# DAC.net
KiCad netlist of a schematic drawn in Altium Designer
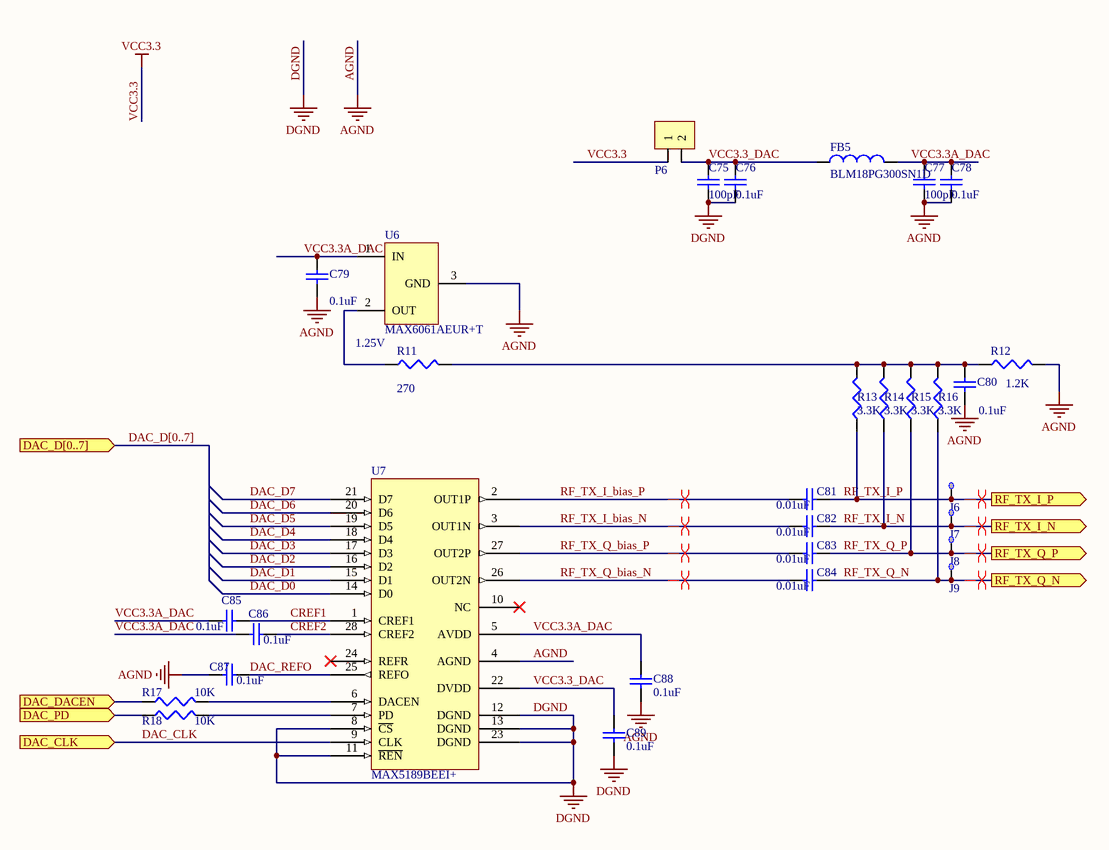
[diagram p0: DAC.SchDoc]

(export (version "E")
  (design (tool "Eeschema 10.0.6"))
  (components
    (comp (ref "C75")
      (value "100pF")
      (footprint "0402")
      (description "Capacitor (Semiconductor SIM Model)")
      (fields (field (name "PUBLISHER") "Altium Limited"))
      (libsource (lib "Miscellaneous Devices") (part "Cap Semi"))
    )
    (comp (ref "C76")
      (value "0.1uF")
      (footprint "0402")
      (description "Capacitor (Semiconductor SIM Model)")
      (fields (field (name "PUBLISHER") "Altium Limited"))
      (libsource (lib "Miscellaneous Devices") (part "Cap Semi"))
    )
    (comp (ref "C77")
      (value "100pF")
      (footprint "0402")
      (description "Capacitor (Semiconductor SIM Model)")
      (fields (field (name "PUBLISHER") "Altium Limited"))
      (libsource (lib "Miscellaneous Devices") (part "Cap Semi"))
    )
    (comp (ref "C78")
      (value "0.1uF")
      (footprint "0402")
      (description "Capacitor (Semiconductor SIM Model)")
      (fields (field (name "PUBLISHER") "Altium Limited"))
      (libsource (lib "Miscellaneous Devices") (part "Cap Semi"))
    )
    (comp (ref "C79")
      (value "0.1uF")
      (footprint "0402")
      (description "Capacitor (Semiconductor SIM Model)")
      (fields (field (name "PUBLISHER") "Altium Limited"))
      (libsource (lib "Miscellaneous Devices") (part "Cap Semi"))
    )
    (comp (ref "C80")
      (value "0.1uF")
      (footprint "0402")
      (description "Capacitor (Semiconductor SIM Model)")
      (fields (field (name "PUBLISHER") "Altium Limited"))
      (libsource (lib "Miscellaneous Devices") (part "Cap Semi"))
    )
    (comp (ref "C81")
      (value "0.01uF")
      (footprint "0402")
      (description "Capacitor (Semiconductor SIM Model)")
      (fields (field (name "PUBLISHER") "Altium Limited"))
      (libsource (lib "Miscellaneous Devices") (part "Cap Semi"))
    )
    (comp (ref "C82")
      (value "0.01uF")
      (footprint "0402")
      (description "Capacitor (Semiconductor SIM Model)")
      (fields (field (name "PUBLISHER") "Altium Limited"))
      (libsource (lib "Miscellaneous Devices") (part "Cap Semi"))
    )
    (comp (ref "C83")
      (value "0.01uF")
      (footprint "0402")
      (description "Capacitor (Semiconductor SIM Model)")
      (fields (field (name "PUBLISHER") "Altium Limited"))
      (libsource (lib "Miscellaneous Devices") (part "Cap Semi"))
    )
    (comp (ref "C84")
      (value "0.01uF")
      (footprint "0402")
      (description "Capacitor (Semiconductor SIM Model)")
      (fields (field (name "PUBLISHER") "Altium Limited"))
      (libsource (lib "Miscellaneous Devices") (part "Cap Semi"))
    )
    (comp (ref "C85")
      (value "0.1uF")
      (footprint "0402")
      (description "Capacitor (Semiconductor SIM Model)")
      (fields (field (name "PUBLISHER") "Altium Limited"))
      (libsource (lib "Miscellaneous Devices") (part "Cap Semi"))
    )
    (comp (ref "C86")
      (value "0.1uF")
      (footprint "0402")
      (description "Capacitor (Semiconductor SIM Model)")
      (fields (field (name "PUBLISHER") "Altium Limited"))
      (libsource (lib "Miscellaneous Devices") (part "Cap Semi"))
    )
    (comp (ref "C87")
      (value "0.1uF")
      (footprint "0402")
      (description "Capacitor (Semiconductor SIM Model)")
      (fields (field (name "PUBLISHER") "Altium Limited"))
      (libsource (lib "Miscellaneous Devices") (part "Cap Semi"))
    )
    (comp (ref "C88")
      (value "0.1uF")
      (footprint "0402")
      (description "Capacitor (Semiconductor SIM Model)")
      (fields (field (name "PUBLISHER") "Altium Limited"))
      (libsource (lib "Miscellaneous Devices") (part "Cap Semi"))
    )
    (comp (ref "C89")
      (value "0.1uF")
      (footprint "0402")
      (description "Capacitor (Semiconductor SIM Model)")
      (fields (field (name "PUBLISHER") "Altium Limited"))
      (libsource (lib "Miscellaneous Devices") (part "Cap Semi"))
    )
    (comp (ref "FB5")
      (value "BLM18PG300SN1D")
      (footprint "1608[0603]")
      (description "FERRITE CHIP 30 OHM 1000MA 0603")
      (libsource (lib "SDR") (part "Ferrite Bead"))
    )
    (comp (ref "J6")
      (value "5004")
      (footprint "TestPoint")
      (description "TEST POINT PC MINI .040\"D YELLOW")
      (libsource (lib "SDR") (part "TestPoint"))
    )
    (comp (ref "J7")
      (value "5004")
      (footprint "TestPoint")
      (description "TEST POINT PC MINI .040\"D YELLOW")
      (libsource (lib "SDR") (part "TestPoint"))
    )
    (comp (ref "J8")
      (value "5004")
      (footprint "TestPoint")
      (description "TEST POINT PC MINI .040\"D YELLOW")
      (libsource (lib "SDR") (part "TestPoint"))
    )
    (comp (ref "J9")
      (value "5004")
      (footprint "TestPoint")
      (description "TEST POINT PC MINI .040\"D YELLOW")
      (libsource (lib "SDR") (part "TestPoint"))
    )
    (comp (ref "P6")
      (value "1 x 2 header")
      (footprint "1x2 header")
      (description "100 mils standard header")
      (libsource (lib "SDR") (part "1 x 2 header"))
    )
    (comp (ref "R11")
      (value "270")
      (footprint "0402")
      (description "Resistor")
      (fields (field (name "PUBLISHER") "Altium Limited"))
      (libsource (lib "Miscellaneous Devices") (part "Res3"))
    )
    (comp (ref "R12")
      (value "1.2K")
      (footprint "0402")
      (description "Resistor")
      (fields (field (name "PUBLISHER") "Altium Limited"))
      (libsource (lib "Miscellaneous Devices") (part "Res3"))
    )
    (comp (ref "R13")
      (value "3.3K")
      (footprint "0402")
      (description "Resistor")
      (fields (field (name "PUBLISHER") "Altium Limited"))
      (libsource (lib "Miscellaneous Devices") (part "Res3"))
    )
    (comp (ref "R14")
      (value "3.3K")
      (footprint "0402")
      (description "Resistor")
      (fields (field (name "PUBLISHER") "Altium Limited"))
      (libsource (lib "Miscellaneous Devices") (part "Res3"))
    )
    (comp (ref "R15")
      (value "3.3K")
      (footprint "0402")
      (description "Resistor")
      (fields (field (name "PUBLISHER") "Altium Limited"))
      (libsource (lib "Miscellaneous Devices") (part "Res3"))
    )
    (comp (ref "R16")
      (value "3.3K")
      (footprint "0402")
      (description "Resistor")
      (fields (field (name "PUBLISHER") "Altium Limited"))
      (libsource (lib "Miscellaneous Devices") (part "Res3"))
    )
    (comp (ref "R17")
      (value "10K")
      (footprint "0402")
      (description "Resistor")
      (fields (field (name "PUBLISHER") "Altium Limited"))
      (libsource (lib "Miscellaneous Devices") (part "Res3"))
    )
    (comp (ref "R18")
      (value "10K")
      (footprint "0402")
      (description "Resistor")
      (fields (field (name "PUBLISHER") "Altium Limited"))
      (libsource (lib "Miscellaneous Devices") (part "Res3"))
    )
    (comp (ref "U6")
      (value "MAX6061AEUR+T")
      (footprint "SOT23-3N")
      (description "IC REF VOLT LDO SOT23-3")
      (fields (field (name "ALTIUM_VALUE") "1.25V"))
      (libsource (lib "SDR") (part "MAX6061"))
    )
    (comp (ref "U7")
      (value "MAX5189BEEI+")
      (footprint "SOP63P600X173-28N")
      (description "IC DAC 8BIT DUAL 40MHZ 28-QSOP")
      (libsource (lib "SDR") (part "MAX5189"))
    )
  )
  (nets
    (net (code "1") (name "/CREF1") (class "Default")
      (node (ref "C85") (pin "2") (pinfunction "2_2") (pintype "passive"))
      (node (ref "U7") (pin "1") (pinfunction "CREF1_1") (pintype "input"))
    )
    (net (code "2") (name "/CREF2") (class "Default")
      (node (ref "C86") (pin "2") (pinfunction "2_2") (pintype "passive"))
      (node (ref "U7") (pin "28") (pinfunction "CREF2_28") (pintype "input"))
    )
    (net (code "3") (name "/DAC_CLK") (class "Default")
      (node (ref "U7") (pin "9") (pinfunction "CLK_9") (pintype "input"))
    )
    (net (code "4") (name "/DAC_D0") (class "Default")
      (node (ref "U7") (pin "14") (pinfunction "D0_14") (pintype "input"))
    )
    (net (code "5") (name "/DAC_D1") (class "Default")
      (node (ref "U7") (pin "15") (pinfunction "D1_15") (pintype "input"))
    )
    (net (code "6") (name "/DAC_D2") (class "Default")
      (node (ref "U7") (pin "16") (pinfunction "D2_16") (pintype "input"))
    )
    (net (code "7") (name "/DAC_D3") (class "Default")
      (node (ref "U7") (pin "17") (pinfunction "D3_17") (pintype "input"))
    )
    (net (code "8") (name "/DAC_D4") (class "Default")
      (node (ref "U7") (pin "18") (pinfunction "D4_18") (pintype "input"))
    )
    (net (code "9") (name "/DAC_D5") (class "Default")
      (node (ref "U7") (pin "19") (pinfunction "D5_19") (pintype "input"))
    )
    (net (code "10") (name "/DAC_D6") (class "Default")
      (node (ref "U7") (pin "20") (pinfunction "D6_20") (pintype "input"))
    )
    (net (code "11") (name "/DAC_D7") (class "Default")
      (node (ref "U7") (pin "21") (pinfunction "D7_21") (pintype "input"))
    )
    (net (code "12") (name "/DAC_DACEN") (class "Default")
      (node (ref "R17") (pin "1") (pinfunction "1_1") (pintype "passive"))
    )
    (net (code "14") (name "/DAC_PD") (class "Default")
      (node (ref "R18") (pin "1") (pinfunction "1_1") (pintype "passive"))
    )
    (net (code "15") (name "/DAC_REFO") (class "Default")
      (node (ref "C87") (pin "2") (pinfunction "2_2") (pintype "passive"))
      (node (ref "U7") (pin "25") (pinfunction "REFO_25") (pintype "output"))
    )
    (net (code "16") (name "/RF_TX_I_N") (class "Default")
      (node (ref "C82") (pin "2") (pinfunction "2_2") (pintype "passive"))
      (node (ref "J7") (pin "1") (pinfunction "TB_1") (pintype "passive"))
      (node (ref "R14") (pin "1") (pinfunction "1_1") (pintype "passive"))
    )
    (net (code "17") (name "/RF_TX_I_P") (class "Default")
      (node (ref "C81") (pin "2") (pinfunction "2_2") (pintype "passive"))
      (node (ref "J6") (pin "1") (pinfunction "TB_1") (pintype "passive"))
      (node (ref "R13") (pin "1") (pinfunction "1_1") (pintype "passive"))
    )
    (net (code "18") (name "/RF_TX_I_bias_N") (class "Default")
      (node (ref "C82") (pin "1") (pinfunction "1_1") (pintype "passive"))
      (node (ref "U7") (pin "3") (pinfunction "OUT1N_3") (pintype "output"))
    )
    (net (code "19") (name "/RF_TX_I_bias_P") (class "Default")
      (node (ref "C81") (pin "1") (pinfunction "1_1") (pintype "passive"))
      (node (ref "U7") (pin "2") (pinfunction "OUT1P_2") (pintype "output"))
    )
    (net (code "20") (name "/RF_TX_Q_N") (class "Default")
      (node (ref "C84") (pin "2") (pinfunction "2_2") (pintype "passive"))
      (node (ref "J9") (pin "1") (pinfunction "TB_1") (pintype "passive"))
      (node (ref "R16") (pin "1") (pinfunction "1_1") (pintype "passive"))
    )
    (net (code "21") (name "/RF_TX_Q_P") (class "Default")
      (node (ref "C83") (pin "2") (pinfunction "2_2") (pintype "passive"))
      (node (ref "J8") (pin "1") (pinfunction "TB_1") (pintype "passive"))
      (node (ref "R15") (pin "1") (pinfunction "1_1") (pintype "passive"))
    )
    (net (code "22") (name "/RF_TX_Q_bias_N") (class "Default")
      (node (ref "C84") (pin "1") (pinfunction "1_1") (pintype "passive"))
      (node (ref "U7") (pin "26") (pinfunction "OUT2N_26") (pintype "output"))
    )
    (net (code "23") (name "/RF_TX_Q_bias_P") (class "Default")
      (node (ref "C83") (pin "1") (pinfunction "1_1") (pintype "passive"))
      (node (ref "U7") (pin "27") (pinfunction "OUT2P_27") (pintype "output"))
    )
    (net (code "24") (name "/VCC3.3A_DAC") (class "Default")
      (node (ref "C77") (pin "2") (pinfunction "2_2") (pintype "passive"))
      (node (ref "C78") (pin "2") (pinfunction "2_2") (pintype "passive"))
      (node (ref "C79") (pin "2") (pinfunction "2_2") (pintype "passive"))
      (node (ref "C85") (pin "1") (pinfunction "1_1") (pintype "passive"))
      (node (ref "C86") (pin "1") (pinfunction "1_1") (pintype "passive"))
      (node (ref "C88") (pin "1") (pinfunction "1_1") (pintype "passive"))
      (node (ref "FB5") (pin "2") (pinfunction "2_2") (pintype "passive"))
      (node (ref "U6") (pin "1") (pinfunction "IN_1") (pintype "passive"))
      (node (ref "U7") (pin "5") (pinfunction "AVDD_5") (pintype "power_in"))
    )
    (net (code "25") (name "/VCC3.3_DAC") (class "Default")
      (node (ref "C75") (pin "2") (pinfunction "2_2") (pintype "passive"))
      (node (ref "C76") (pin "2") (pinfunction "2_2") (pintype "passive"))
      (node (ref "C89") (pin "1") (pinfunction "1_1") (pintype "passive"))
      (node (ref "FB5") (pin "1") (pinfunction "1_1") (pintype "passive"))
      (node (ref "P6") (pin "2") (pinfunction "2_2") (pintype "passive"))
      (node (ref "U7") (pin "22") (pinfunction "DVDD_22") (pintype "power_in"))
    )
    (net (code "26") (name "AGND") (class "Default")
      (node (ref "C77") (pin "1") (pinfunction "1_1") (pintype "passive"))
      (node (ref "C78") (pin "1") (pinfunction "1_1") (pintype "passive"))
      (node (ref "C79") (pin "1") (pinfunction "1_1") (pintype "passive"))
      (node (ref "C80") (pin "1") (pinfunction "1_1") (pintype "passive"))
      (node (ref "C87") (pin "1") (pinfunction "1_1") (pintype "passive"))
      (node (ref "C88") (pin "2") (pinfunction "2_2") (pintype "passive"))
      (node (ref "R12") (pin "2") (pinfunction "2_2") (pintype "passive"))
      (node (ref "U6") (pin "3") (pinfunction "GND_3") (pintype "power_in"))
      (node (ref "U7") (pin "4") (pinfunction "AGND_4") (pintype "power_in"))
    )
    (net (code "27") (name "DGND") (class "Default")
      (node (ref "C75") (pin "1") (pinfunction "1_1") (pintype "passive"))
      (node (ref "C76") (pin "1") (pinfunction "1_1") (pintype "passive"))
      (node (ref "C89") (pin "2") (pinfunction "2_2") (pintype "passive"))
      (node (ref "U7") (pin "11") (pinfunction "~{REN}_11") (pintype "input"))
      (node (ref "U7") (pin "12") (pinfunction "DGND_12") (pintype "power_in"))
      (node (ref "U7") (pin "13") (pinfunction "DGND_13") (pintype "power_in"))
      (node (ref "U7") (pin "23") (pinfunction "DGND_23") (pintype "power_in"))
      (node (ref "U7") (pin "8") (pinfunction "~{CS}_8") (pintype "input"))
    )
    (net (code "28") (name "Net-(C80-Pad2)") (class "Default")
      (node (ref "C80") (pin "2") (pinfunction "2_2") (pintype "passive"))
      (node (ref "R11") (pin "2") (pinfunction "2_2") (pintype "passive"))
      (node (ref "R12") (pin "1") (pinfunction "1_1") (pintype "passive"))
      (node (ref "R13") (pin "2") (pinfunction "2_2") (pintype "passive"))
      (node (ref "R14") (pin "2") (pinfunction "2_2") (pintype "passive"))
      (node (ref "R15") (pin "2") (pinfunction "2_2") (pintype "passive"))
      (node (ref "R16") (pin "2") (pinfunction "2_2") (pintype "passive"))
    )
    (net (code "29") (name "Net-(U6-OUT)") (class "Default")
      (node (ref "R11") (pin "1") (pinfunction "1_1") (pintype "passive"))
      (node (ref "U6") (pin "2") (pinfunction "OUT_2") (pintype "passive"))
    )
    (net (code "30") (name "Net-(U7-DACEN)") (class "Default")
      (node (ref "R17") (pin "2") (pinfunction "2_2") (pintype "passive"))
      (node (ref "U7") (pin "6") (pinfunction "DACEN_6") (pintype "input"))
    )
    (net (code "31") (name "Net-(U7-PD)") (class "Default")
      (node (ref "R18") (pin "2") (pinfunction "2_2") (pintype "passive"))
      (node (ref "U7") (pin "7") (pinfunction "PD_7") (pintype "input"))
    )
    (net (code "32") (name "VCC3.3") (class "Default")
      (node (ref "P6") (pin "1") (pinfunction "1_1") (pintype "passive"))
    )
    (net (code "33") (name "unconnected-(U7-NC-Pad10)") (class "Default")
      (node (ref "U7") (pin "10") (pinfunction "NC_10") (pintype "passive+no_connect"))
    )
    (net (code "34") (name "unconnected-(U7-REFR-Pad24)") (class "Default")
      (node (ref "U7") (pin "24") (pinfunction "REFR_24") (pintype "input+no_connect"))
    )
  )
)
